# mishen.net
KiCad netlist of a schematic drawn in Altium Designer
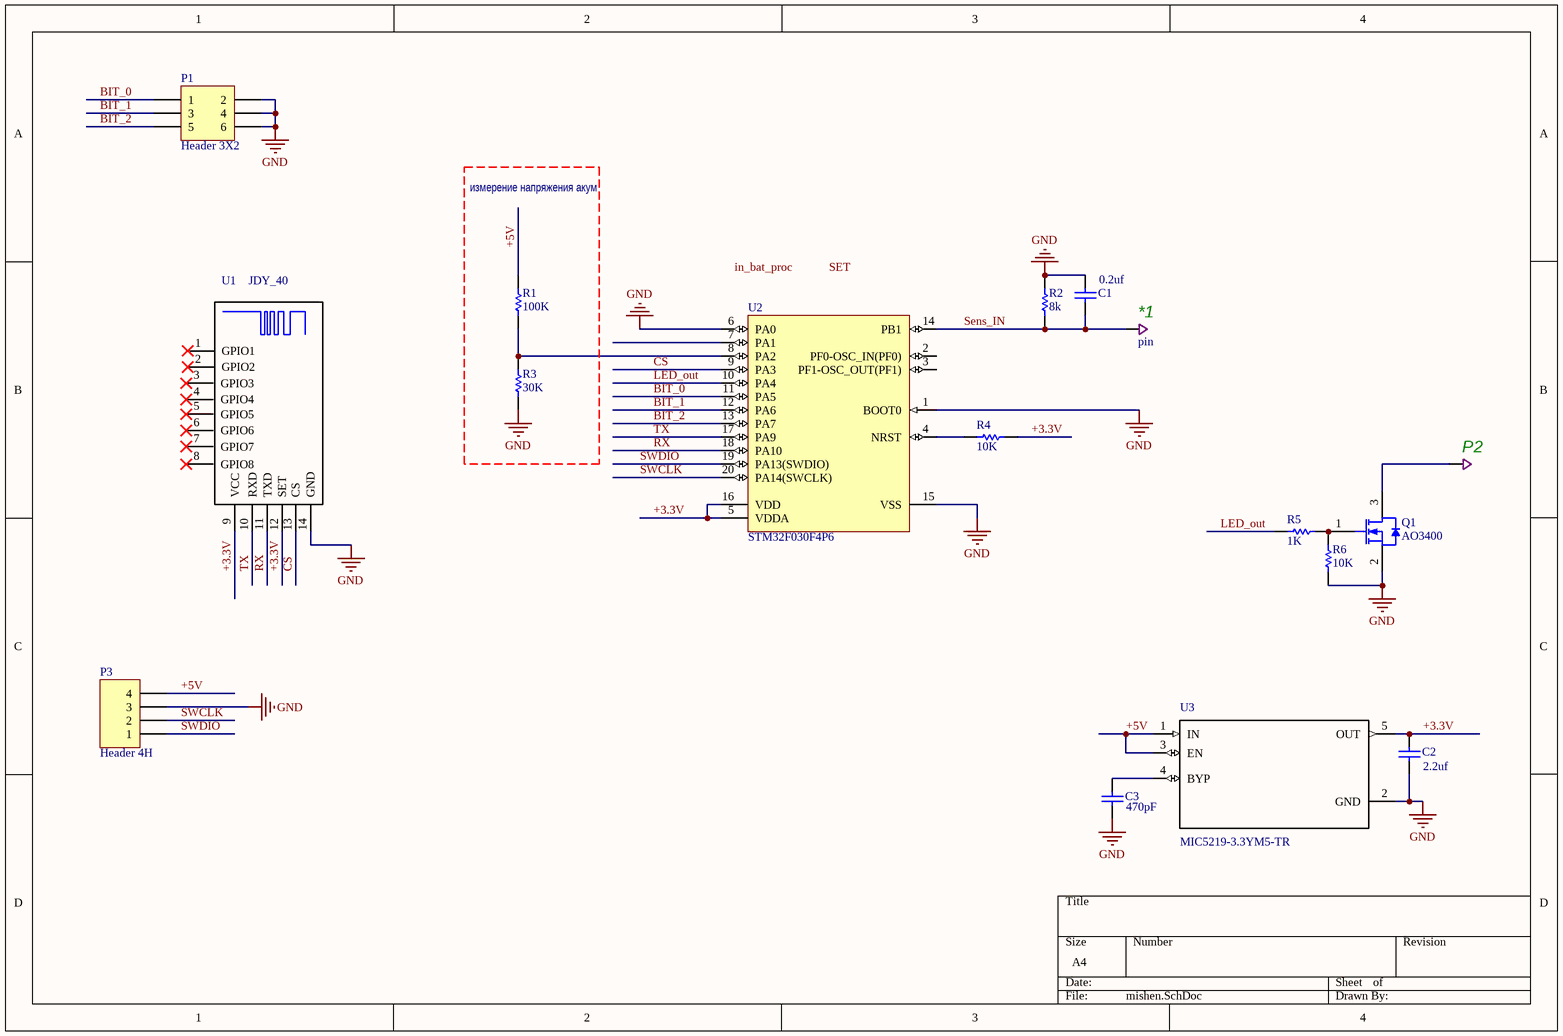
[diagram p0: mishen.SchDoc]

(export (version "E")
  (design (tool "Eeschema 10.0.6"))
  (components
    (comp (ref "*1") (value "pin") (footprint "pin") (libsource (lib "moya") (part "pin")))
    (comp (ref "C1")
      (value "0.2uf")
      (footprint "CAPC0603(1608)100_L")
      (description "0603 (1608 Metric) Chip Capacitor")
      (libsource (lib "Altium Content Vault") (part "CAP_5"))
    )
    (comp (ref "C2")
      (value "2.2uf")
      (footprint "CAPC0603(1608)100_L")
      (description "0603 (1608 Metric) Chip Capacitor")
      (libsource (lib "Altium Content Vault") (part "CAP_5"))
    )
    (comp (ref "C3")
      (value "470pF")
      (footprint "CAPC0603(1608)100_L")
      (description "0603 (1608 Metric) Chip Capacitor")
      (libsource (lib "Altium Content Vault") (part "CAP_5"))
    )
    (comp (ref "P1")
      (value "Header 3X2")
      (footprint "HDR2X3")
      (description "Header, 3-Pin, Dual row")
      (fields (field (name "PUBLISHER") "Altium Limited"))
      (libsource (lib "Miscellaneous Connectors") (part "Header 3X2"))
    )
    (comp (ref "P2") (value "pin") (footprint "pin") (libsource (lib "moya") (part "pin")))
    (comp (ref "P3")
      (value "Header 4H")
      (footprint "HDR1X4H")
      (description "Header, 4-Pin, Right Angle")
      (fields (field (name "PUBLISHER") "Altium Limited"))
      (libsource (lib "Miscellaneous Connectors") (part "Header 4H"))
    )
    (comp (ref "Q1")
      (value "AO3400")
      (footprint "AO-SOT23-3_V")
      (description "N-channel Enhancement Mode Field-Effect Transistor; 5.8A/30V")
      (fields (field (name "MANUFACTURER") "Alpha and Omega"))
      (libsource (lib "Altium Content Vault") (part "AO-NEMOS-G1S2D3-3"))
    )
    (comp (ref "R1")
      (value "100K")
      (footprint "RESC2013X70X40ML20T20")
      (description "RES SMD 150K OHM 1% 1/8W 0805")
      (fields (field (name "MANUFACTURER") "Panasonic") (field (name "PART NUMBER") "ERJ-6ENF1503V"))
      (libsource (lib "Altium Content Vault") (part "CMP-2001-04440-2"))
    )
    (comp (ref "R2")
      (value "8k")
      (footprint "RESC2013X70X40ML20T20")
      (description "RES SMD 150K OHM 1% 1/8W 0805")
      (fields (field (name "MANUFACTURER") "Panasonic") (field (name "PART NUMBER") "ERJ-6ENF1503V"))
      (libsource (lib "Altium Content Vault") (part "CMP-2001-04440-2"))
    )
    (comp (ref "R3")
      (value "30K")
      (footprint "RESC2013X70X40ML20T20")
      (description "RES SMD 150K OHM 1% 1/8W 0805")
      (fields (field (name "MANUFACTURER") "Panasonic") (field (name "PART NUMBER") "ERJ-6ENF1503V"))
      (libsource (lib "Altium Content Vault") (part "CMP-2001-04440-2"))
    )
    (comp (ref "R4")
      (value "10K")
      (footprint "RESC2013X70X40ML20T20")
      (description "RES SMD 150K OHM 1% 1/8W 0805")
      (fields (field (name "MANUFACTURER") "Panasonic") (field (name "PART NUMBER") "ERJ-6ENF1503V"))
      (libsource (lib "Altium Content Vault") (part "CMP-2001-04440-2"))
    )
    (comp (ref "R5")
      (value "1K")
      (footprint "RESC2013X70X40ML20T20")
      (description "RES SMD 150K OHM 1% 1/8W 0805")
      (fields (field (name "MANUFACTURER") "Panasonic") (field (name "PART NUMBER") "ERJ-6ENF1503V"))
      (libsource (lib "Altium Content Vault") (part "CMP-2001-04440-2"))
    )
    (comp (ref "R6")
      (value "10K")
      (footprint "RESC2013X70X40ML20T20")
      (description "RES SMD 150K OHM 1% 1/8W 0805")
      (fields (field (name "MANUFACTURER") "Panasonic") (field (name "PART NUMBER") "ERJ-6ENF1503V"))
      (libsource (lib "Altium Content Vault") (part "CMP-2001-04440-2"))
    )
    (comp (ref "U1")
      (value "JDY_40")
      (footprint "JDY_40")
      (fields (field (name "MF") "Advanced Monolithic Systems"))
      (libsource (lib "moya") (part "JDY_40"))
    )
    (comp (ref "U2")
      (value "STM32F030F4P6")
      (footprint "STM-TSSOP20_N")
      (libsource (lib "Altium Content Vault") (part "CMP-0304-00039-2"))
    )
    (comp (ref "U3")
      (value "MIC5219-3.3YM5-TR")
      (footprint "mic51")
      (description "MIC5219 Series 500 mA 3.3 V Fixed Output Surface Mount LDO Regulator - SOT-23-5")
      (fields (field (name "MF") "Microchip"))
      (libsource (lib "moya") (part "MIC5219-3.3YM5-TR"))
    )
  )
  (nets
    (net (code "1") (name "/+3.3V") (class "Default")
      (node (ref "C2") (pin "2") (pinfunction "2_2") (pintype "passive"))
      (node (ref "R4") (pin "1") (pinfunction "1_1") (pintype "passive"))
      (node (ref "U1") (pin "12") (pinfunction "SET_12") (pintype "power_in"))
      (node (ref "U1") (pin "9") (pinfunction "VCC_9") (pintype "power_in"))
      (node (ref "U2") (pin "16") (pinfunction "VDD_16") (pintype "power_in"))
      (node (ref "U2") (pin "5") (pinfunction "VDDA_5") (pintype "power_in"))
      (node (ref "U3") (pin "5") (pinfunction "OUT_5") (pintype "output"))
    )
    (net (code "2") (name "/+5V") (class "Default")
      (node (ref "P3") (pin "4") (pinfunction "4_4") (pintype "passive"))
      (node (ref "R1") (pin "1") (pinfunction "1_1") (pintype "passive"))
      (node (ref "U3") (pin "1") (pinfunction "IN_1") (pintype "input"))
      (node (ref "U3") (pin "3") (pinfunction "EN_3") (pintype "bidirectional"))
    )
    (net (code "3") (name "/BIT_0") (class "Default")
      (node (ref "P1") (pin "1") (pinfunction "1_1") (pintype "passive"))
      (node (ref "U2") (pin "11") (pinfunction "PA5_11") (pintype "bidirectional"))
    )
    (net (code "4") (name "/BIT_1") (class "Default")
      (node (ref "P1") (pin "3") (pinfunction "3_3") (pintype "passive"))
      (node (ref "U2") (pin "12") (pinfunction "PA6_12") (pintype "bidirectional"))
    )
    (net (code "5") (name "/BIT_2") (class "Default")
      (node (ref "P1") (pin "5") (pinfunction "5_5") (pintype "passive"))
      (node (ref "U2") (pin "13") (pinfunction "PA7_13") (pintype "bidirectional"))
    )
    (net (code "6") (name "/CS") (class "Default")
      (node (ref "U1") (pin "13") (pinfunction "CS_13") (pintype "power_in"))
      (node (ref "U2") (pin "9") (pinfunction "PA3_9") (pintype "bidirectional"))
    )
    (net (code "7") (name "/LED_out") (class "Default")
      (node (ref "R5") (pin "2") (pinfunction "2_2") (pintype "passive"))
      (node (ref "U2") (pin "10") (pinfunction "PA4_10") (pintype "bidirectional"))
    )
    (net (code "8") (name "/RX") (class "Default")
      (node (ref "U1") (pin "11") (pinfunction "TXD_11") (pintype "power_in"))
      (node (ref "U2") (pin "18") (pinfunction "PA10_18") (pintype "bidirectional"))
    )
    (net (code "10") (name "/SWCLK") (class "Default")
      (node (ref "P3") (pin "2") (pinfunction "2_2") (pintype "passive"))
      (node (ref "U2") (pin "20") (pinfunction "PA14(SWCLK)_20") (pintype "bidirectional"))
    )
    (net (code "11") (name "/SWDIO") (class "Default")
      (node (ref "P3") (pin "1") (pinfunction "1_1") (pintype "passive"))
      (node (ref "U2") (pin "19") (pinfunction "PA13(SWDIO)_19") (pintype "bidirectional"))
    )
    (net (code "12") (name "/Sens_IN") (class "Default")
      (node (ref "*1") (pin "0") (pinfunction "0_0") (pintype "passive"))
      (node (ref "C1") (pin "1") (pinfunction "1_1") (pintype "passive"))
      (node (ref "R2") (pin "2") (pinfunction "2_2") (pintype "passive"))
      (node (ref "U2") (pin "14") (pinfunction "PB1_14") (pintype "bidirectional"))
    )
    (net (code "13") (name "/TX") (class "Default")
      (node (ref "U1") (pin "10") (pinfunction "RXD_10") (pintype "power_in"))
      (node (ref "U2") (pin "17") (pinfunction "PA9_17") (pintype "bidirectional"))
    )
    (net (code "15") (name "GND") (class "Default")
      (node (ref "C1") (pin "2") (pinfunction "2_2") (pintype "passive"))
      (node (ref "C2") (pin "1") (pinfunction "1_1") (pintype "passive"))
      (node (ref "C3") (pin "1") (pinfunction "1_1") (pintype "passive"))
      (node (ref "P1") (pin "2") (pinfunction "2_2") (pintype "passive"))
      (node (ref "P1") (pin "4") (pinfunction "4_4") (pintype "passive"))
      (node (ref "P1") (pin "6") (pinfunction "6_6") (pintype "passive"))
      (node (ref "P3") (pin "3") (pinfunction "3_3") (pintype "passive"))
      (node (ref "Q1") (pin "2") (pinfunction "S_2") (pintype "passive"))
      (node (ref "R2") (pin "1") (pinfunction "1_1") (pintype "passive"))
      (node (ref "R3") (pin "2") (pinfunction "2_2") (pintype "passive"))
      (node (ref "R6") (pin "2") (pinfunction "2_2") (pintype "passive"))
      (node (ref "U1") (pin "14") (pinfunction "GND_14") (pintype "power_in"))
      (node (ref "U2") (pin "1") (pinfunction "BOOT0_1") (pintype "input"))
      (node (ref "U2") (pin "15") (pinfunction "VSS_15") (pintype "power_in"))
      (node (ref "U2") (pin "6") (pinfunction "PA0_6") (pintype "bidirectional"))
      (node (ref "U3") (pin "2") (pinfunction "GND_2") (pintype "power_in"))
    )
    (net (code "16") (name "Net-(Q1-D)") (class "Default")
      (node (ref "P2") (pin "0") (pinfunction "0_0") (pintype "passive"))
      (node (ref "Q1") (pin "3") (pinfunction "D_3") (pintype "passive"))
    )
    (net (code "17") (name "Net-(Q1-G)") (class "Default")
      (node (ref "Q1") (pin "1") (pinfunction "G_1") (pintype "passive"))
      (node (ref "R5") (pin "1") (pinfunction "1_1") (pintype "passive"))
      (node (ref "R6") (pin "1") (pinfunction "1_1") (pintype "passive"))
    )
    (net (code "18") (name "Net-(U2-NRST)") (class "Default")
      (node (ref "R4") (pin "2") (pinfunction "2_2") (pintype "passive"))
      (node (ref "U2") (pin "4") (pinfunction "NRST_4") (pintype "bidirectional"))
    )
    (net (code "19") (name "Net-(U2-PA2)") (class "Default")
      (node (ref "R1") (pin "2") (pinfunction "2_2") (pintype "passive"))
      (node (ref "R3") (pin "1") (pinfunction "1_1") (pintype "passive"))
      (node (ref "U2") (pin "8") (pinfunction "PA2_8") (pintype "bidirectional"))
    )
    (net (code "20") (name "Net-(U3-BYP)") (class "Default")
      (node (ref "C3") (pin "2") (pinfunction "2_2") (pintype "passive"))
      (node (ref "U3") (pin "4") (pinfunction "BYP_4") (pintype "bidirectional"))
    )
    (net (code "21") (name "unconnected-(U1-GPIO1-Pad1)") (class "Default")
      (node (ref "U1") (pin "1") (pinfunction "GPIO1_1") (pintype "power_in+no_connect"))
    )
    (net (code "22") (name "unconnected-(U1-GPIO2-Pad2)") (class "Default")
      (node (ref "U1") (pin "2") (pinfunction "GPIO2_2") (pintype "power_in+no_connect"))
    )
    (net (code "23") (name "unconnected-(U1-GPIO3-Pad3)") (class "Default")
      (node (ref "U1") (pin "3") (pinfunction "GPIO3_3") (pintype "power_in+no_connect"))
    )
    (net (code "24") (name "unconnected-(U1-GPIO4-Pad4)") (class "Default")
      (node (ref "U1") (pin "4") (pinfunction "GPIO4_4") (pintype "power_in+no_connect"))
    )
    (net (code "25") (name "unconnected-(U1-GPIO5-Pad5)") (class "Default")
      (node (ref "U1") (pin "5") (pinfunction "GPIO5_5") (pintype "power_in+no_connect"))
    )
    (net (code "26") (name "unconnected-(U1-GPIO6-Pad6)") (class "Default")
      (node (ref "U1") (pin "6") (pinfunction "GPIO6_6") (pintype "power_in+no_connect"))
    )
    (net (code "27") (name "unconnected-(U1-GPIO7-Pad7)") (class "Default")
      (node (ref "U1") (pin "7") (pinfunction "GPIO7_7") (pintype "power_in+no_connect"))
    )
    (net (code "28") (name "unconnected-(U1-GPIO8-Pad8)") (class "Default")
      (node (ref "U1") (pin "8") (pinfunction "GPIO8_8") (pintype "power_in+no_connect"))
    )
    (net (code "29") (name "unconnected-(U2-PA1-Pad7)") (class "Default")
      (node (ref "U2") (pin "7") (pinfunction "PA1_7") (pintype "bidirectional"))
    )
    (net (code "30") (name "unconnected-(U2-PF0-OSC_IN(PF0)-Pad2)") (class "Default")
      (node (ref "U2") (pin "2") (pinfunction "PF0-OSC_IN(PF0)_2") (pintype "bidirectional"))
    )
    (net (code "31") (name "unconnected-(U2-PF1-OSC_OUT(PF1)-Pad3)") (class "Default")
      (node (ref "U2") (pin "3") (pinfunction "PF1-OSC_OUT(PF1)_3") (pintype "bidirectional"))
    )
  )
)
